# SWD.net
KiCad netlist of a schematic drawn in Altium Designer
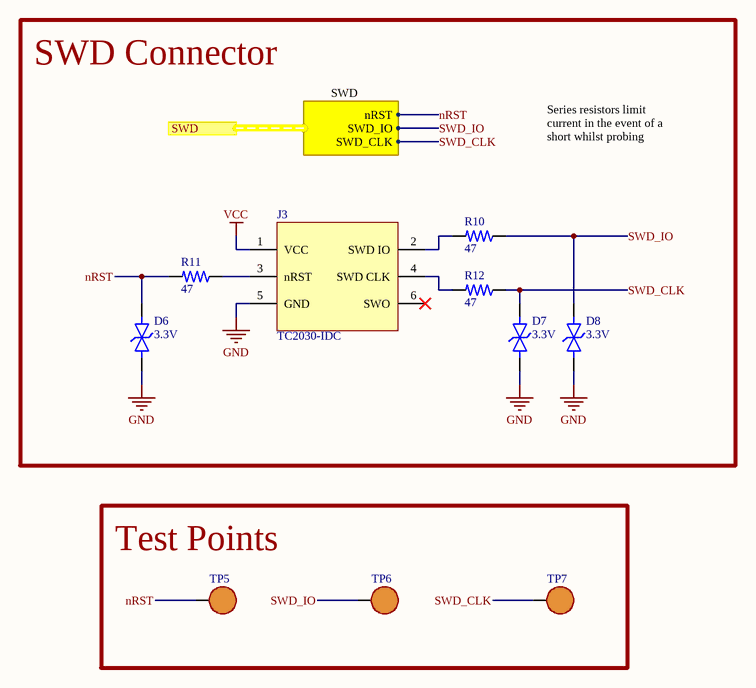
[diagram p0: SWD.SchDoc]

(export (version "E")
  (design (tool "Eeschema 10.0.6"))
  (components
    (comp (ref "D6")
      (value "DESD3V3E1BL-7B")
      (footprint "Beethoven-clock:0402-TVS")
      (description "TVS DIODE 3.3VWM 7VC DFN1006-2")
      (fields (field (name "MFR") "Diodes Incorporated") (field (name "VRS") "3.3V"))
      (libsource (lib "Beethoven-clock") (part "TVS Diode 3.3V Bi"))
    )
    (comp (ref "D7")
      (value "DESD3V3E1BL-7B")
      (footprint "Beethoven-clock:0402-TVS")
      (description "TVS DIODE 3.3VWM 7VC DFN1006-2")
      (fields (field (name "MFR") "Diodes Incorporated") (field (name "VRS") "3.3V"))
      (libsource (lib "Beethoven-clock") (part "TVS Diode 3.3V Bi"))
    )
    (comp (ref "D8")
      (value "DESD3V3E1BL-7B")
      (footprint "Beethoven-clock:0402-TVS")
      (description "TVS DIODE 3.3VWM 7VC DFN1006-2")
      (fields (field (name "MFR") "Diodes Incorporated") (field (name "VRS") "3.3V"))
      (libsource (lib "Beethoven-clock") (part "TVS Diode 3.3V Bi"))
    )
    (comp (ref "J3")
      (value "TC2030-IDC")
      (footprint "Beethoven-clock:TAG CONNECT TC2030IDC - NO 3D MODEL")
      (description "\"Plug of Nails\" POGO Pin connector")
      (fields (field (name "MFR") "Tag-Connect"))
      (libsource (lib "Beethoven-clock") (part "TC2030-IDC"))
    )
    (comp (ref "R10")
      (value "47")
      (footprint "Beethoven-clock:0402R")
      (description "Resistor")
      (fields (field (name "MFR") "YAGEO") (field (name "Comment") "RES"))
      (libsource (lib "Beethoven-clock") (part "RES"))
    )
    (comp (ref "R11")
      (value "47")
      (footprint "Beethoven-clock:0402R")
      (description "Resistor")
      (fields (field (name "MFR") "YAGEO") (field (name "Comment") "RES"))
      (libsource (lib "Beethoven-clock") (part "RES"))
    )
    (comp (ref "R12")
      (value "47")
      (footprint "Beethoven-clock:0402R")
      (description "Resistor")
      (fields (field (name "MFR") "YAGEO") (field (name "Comment") "RES"))
      (libsource (lib "Beethoven-clock") (part "RES"))
    )
    (comp (ref "TP5")
      (value "RCWCTE")
      (footprint "Beethoven-clock:RCWCTE")
      (description "Test Point, Surface Mount")
      (fields (field (name "MFR") "KOA Speer Electronics, Inc."))
      (libsource (lib "Beethoven-clock") (part "TEST POINT"))
    )
    (comp (ref "TP6")
      (value "RCWCTE")
      (footprint "Beethoven-clock:RCWCTE")
      (description "Test Point, Surface Mount")
      (fields (field (name "MFR") "KOA Speer Electronics, Inc."))
      (libsource (lib "Beethoven-clock") (part "TEST POINT"))
    )
    (comp (ref "TP7")
      (value "RCWCTE")
      (footprint "Beethoven-clock:RCWCTE")
      (description "Test Point, Surface Mount")
      (fields (field (name "MFR") "KOA Speer Electronics, Inc."))
      (libsource (lib "Beethoven-clock") (part "TEST POINT"))
    )
  )
  (nets
    (net (code "2") (name "/SWD_CLK") (class "Default")
      (node (ref "D7") (pin "1") (pinfunction "1_1") (pintype "passive"))
      (node (ref "R12") (pin "1") (pinfunction "1_1") (pintype "passive"))
      (node (ref "TP7") (pin "1") (pinfunction "0_1") (pintype "passive"))
    )
    (net (code "3") (name "/SWD_IO") (class "Default")
      (node (ref "D8") (pin "1") (pinfunction "1_1") (pintype "passive"))
      (node (ref "R10") (pin "1") (pinfunction "1_1") (pintype "passive"))
      (node (ref "TP6") (pin "1") (pinfunction "0_1") (pintype "passive"))
    )
    (net (code "4") (name "/nRST") (class "Default")
      (node (ref "D6") (pin "1") (pinfunction "1_1") (pintype "passive"))
      (node (ref "R11") (pin "2") (pinfunction "2_2") (pintype "passive"))
      (node (ref "TP5") (pin "1") (pinfunction "0_1") (pintype "passive"))
    )
    (net (code "6") (name "GND") (class "Default")
      (node (ref "D6") (pin "2") (pinfunction "2_2") (pintype "passive"))
      (node (ref "D7") (pin "2") (pinfunction "2_2") (pintype "passive"))
      (node (ref "D8") (pin "2") (pinfunction "2_2") (pintype "passive"))
      (node (ref "J3") (pin "5") (pinfunction "GND_5") (pintype "passive"))
    )
    (net (code "7") (name "Net-(J3-SWD_CLK)") (class "Default")
      (node (ref "J3") (pin "4") (pinfunction "SWD_CLK_4") (pintype "passive"))
      (node (ref "R12") (pin "2") (pinfunction "2_2") (pintype "passive"))
    )
    (net (code "8") (name "Net-(J3-SWD_IO)") (class "Default")
      (node (ref "J3") (pin "2") (pinfunction "SWD_IO_2") (pintype "passive"))
      (node (ref "R10") (pin "2") (pinfunction "2_2") (pintype "passive"))
    )
    (net (code "9") (name "Net-(J3-nRST)") (class "Default")
      (node (ref "J3") (pin "3") (pinfunction "nRST_3") (pintype "passive"))
      (node (ref "R11") (pin "1") (pinfunction "1_1") (pintype "passive"))
    )
    (net (code "10") (name "VCC") (class "Default")
      (node (ref "J3") (pin "1") (pinfunction "VCC_1") (pintype "passive"))
    )
    (net (code "11") (name "unconnected-(J3-SWO-Pad6)") (class "Default")
      (node (ref "J3") (pin "6") (pinfunction "SWO_6") (pintype "passive+no_connect"))
    )
  )
)
